# 3V3.net
KiCad netlist of a schematic drawn in Altium Designer
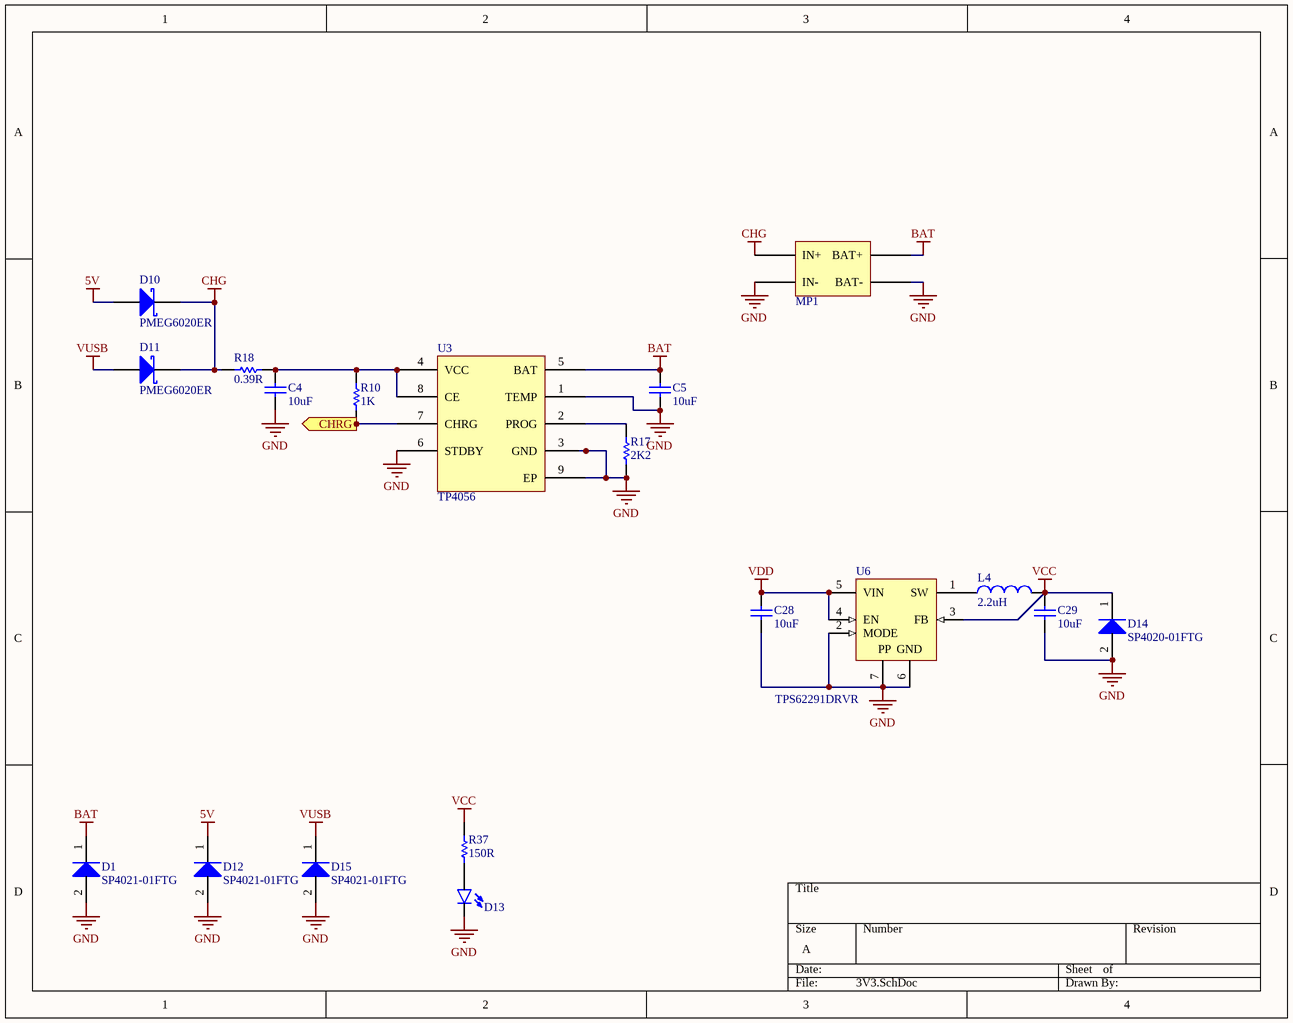
[diagram p0: 3V3.SchDoc]

(export (version "E")
  (design (tool "Eeschema 10.0.6"))
  (components
    (comp (ref "C4")
      (value "10uF")
      (footprint "C1206[3216X160]")
      (description "10uF 50V 20% 1206 (3216 Metric)")
      (fields (field (name "PARTNUMBER") "UMK316BBJ106ML-T") (field (name "MANUFACTURER") "Taiyo Yuden"))
      (libsource (lib "Capacitors") (part "CAP_10uF_50V_1206_20%"))
    )
    (comp (ref "C5")
      (value "10uF")
      (footprint "C1206[3216X160]")
      (description "10uF 50V 20% 1206 (3216 Metric)")
      (fields (field (name "PARTNUMBER") "UMK316BBJ106ML-T") (field (name "MANUFACTURER") "Taiyo Yuden"))
      (libsource (lib "Capacitors") (part "CAP_10uF_50V_1206_20%"))
    )
    (comp (ref "C28")
      (value "10uF")
      (footprint "C0603[1608X92]")
      (description "10uF 16V 10% 0603 (1608 Metric)")
      (fields (field (name "PARTNUMBER") "GRM188R61C106KAALD") (field (name "MANUFACTURER") "Murata"))
      (libsource (lib "Capacitors") (part "CAP_10uF_16V_0603_10%"))
    )
    (comp (ref "C29")
      (value "10uF")
      (footprint "C0603[1608X92]")
      (description "10uF 6.3V 10% 0603 (1608 Metric)")
      (fields (field (name "PARTNUMBER") "GRM188R60J106KE47D") (field (name "MANUFACTURER") "Murata"))
      (libsource (lib "Capacitors") (part "CAP_10uF_6.3V_0603_10%"))
    )
    (comp (ref "D1")
      (value "SP4021-01FTG")
      (footprint "SOD-323")
      (fields (field (name "MANUFACTURER") "Littelfuse"))
      (libsource (lib "Diodes") (part "SP4021-01FTG"))
    )
    (comp (ref "D10")
      (value "PMEG6020ER")
      (footprint "SOD-123")
      (fields (field (name "PARTNUMBER") "PMEG6020ER,115") (field (name "MANUFACTURER") "NXP Semiconductors"))
      (libsource (lib "Diodes") (part "PMEG6020ER"))
    )
    (comp (ref "D11")
      (value "PMEG6020ER")
      (footprint "SOD-123")
      (fields (field (name "PARTNUMBER") "PMEG6020ER,115") (field (name "MANUFACTURER") "NXP Semiconductors"))
      (libsource (lib "Diodes") (part "PMEG6020ER"))
    )
    (comp (ref "D12")
      (value "SP4021-01FTG")
      (footprint "SOD-323")
      (fields (field (name "MANUFACTURER") "Littelfuse"))
      (libsource (lib "Diodes") (part "SP4021-01FTG"))
    )
    (comp (ref "D13")
      (value "LED_0603_GREEN_5mA")
      (footprint "LED0603")
      (fields (field (name "PARTNUMBER") "LTST-C193TGKT-5A") (field (name "MANUFACTURER") "Lite-On Inc."))
      (libsource (lib "LEDs") (part "LED_0603_GREEN_5mA"))
    )
    (comp (ref "D14")
      (value "SP4020-01FTG")
      (footprint "SOD-323")
      (fields (field (name "MANUFACTURER") "Littelfuse"))
      (libsource (lib "Diodes") (part "SP4020-01FTG"))
    )
    (comp (ref "D15")
      (value "SP4021-01FTG")
      (footprint "SOD-323")
      (fields (field (name "MANUFACTURER") "Littelfuse"))
      (libsource (lib "Diodes") (part "SP4021-01FTG"))
    )
    (comp (ref "L4")
      (value "2.2uH")
      (footprint "IND0805")
      (description "2.2uH 20% 1.7A 0805")
      (fields (field (name "PARTNUMBER") "LQM21PN2R2MGHL") (field (name "MANUFACTURER") "Murata"))
      (libsource (lib "Inductors") (part "IND_2.2uH_1.7A_0805_20%"))
    )
    (comp (ref "MP1")
      (value "Li-ion CHARGER")
      (footprint "LI-ION CHARGER")
      (description "TP4056 LI-ION, LI-POLYMER 1-CELL CHARGER")
      (fields (field (name "MANUFACTURER") "ELEPARTS") (field (name "PARTNUMBER") "Micro USB 1A"))
      (libsource (lib "Components") (part "Li-ion CHARGER"))
    )
    (comp (ref "R10")
      (value "1K")
      (footprint "R0603[1608]")
      (description "1K 0.25W 1% 0603 (1005 Metric)")
      (fields (field (name "MANUFACTURER") "Vishay / Dale") (field (name "PARTNUMBER") "CRCW06031K00FKEAHP"))
      (libsource (lib "Resistors") (part "RES_1K_0603_1%"))
    )
    (comp (ref "R17")
      (value "2K2")
      (footprint "R0603[1608]")
      (description "2K2 0.25W 1% 0603 (1005 Metric)")
      (fields (field (name "MANUFACTURER") "Vishay / Dale") (field (name "PARTNUMBER") "CRCW06032K20FKEAHP"))
      (libsource (lib "Resistors") (part "RES_2K2_0603_1%"))
    )
    (comp (ref "R18")
      (value "0.39R")
      (footprint "R1206[3216]")
      (description "0.39R 0.5W 1% 1206 (3216 Metric)")
      (fields (field (name "MANUFACTURER") "Vishay Dale") (field (name "PARTNUMBER") "RCWE1206R390FKEA"))
      (libsource (lib "Resistors") (part "RES_0.39R_1206_1%"))
    )
    (comp (ref "R37")
      (value "150R")
      (footprint "R0603[1608]")
      (description "150R 0.25W 1% 0603 (1005 Metric)")
      (fields (field (name "MANUFACTURER") "Vishay / Dale") (field (name "PARTNUMBER") "CRCW0603150RFKEAHP"))
      (libsource (lib "Resistors") (part "RES_150R_0603_1%"))
    )
    (comp (ref "U3")
      (value "TP4056")
      (footprint "SOIC-8-EP")
      (description "1 CELL Li-ion Battery Charger")
      (fields (field (name "MANUFACTURER") "Nanjing Extension Microelectronics"))
      (libsource (lib "ICs") (part "TP4056"))
    )
    (comp (ref "U6")
      (value "TPS62291DRVR")
      (footprint "WSON-6")
      (description "Voltage Regulators - Switching Regulators 2.25MHz 1A Step-Down Cnvrtr 3.3V Output")
      (fields (field (name "MANUFACTURER") "Texas Instruments"))
      (libsource (lib "ICs") (part "TPS62291DRVR"))
    )
  )
  (nets
    (net (code "1") (name "/CHRG") (class "Default")
      (node (ref "R10") (pin "1") (pinfunction "1_1") (pintype "passive"))
      (node (ref "U3") (pin "7") (pinfunction "CHRG_7") (pintype "passive"))
    )
    (net (code "2") (name "5V") (class "Default")
      (node (ref "D10") (pin "2") (pinfunction "A_2") (pintype "passive"))
      (node (ref "D12") (pin "1") (pinfunction "K_1") (pintype "passive"))
    )
    (net (code "3") (name "BAT") (class "Default")
      (node (ref "C5") (pin "2") (pinfunction "2_2") (pintype "passive"))
      (node (ref "D1") (pin "1") (pinfunction "K_1") (pintype "passive"))
      (node (ref "MP1") (pin "3") (pinfunction "BAT+_3") (pintype "passive"))
      (node (ref "U3") (pin "5") (pinfunction "BAT_5") (pintype "passive"))
    )
    (net (code "4") (name "CHG") (class "Default")
      (node (ref "D10") (pin "1") (pinfunction "K_1") (pintype "passive"))
      (node (ref "D11") (pin "1") (pinfunction "K_1") (pintype "passive"))
      (node (ref "MP1") (pin "1") (pinfunction "IN+_1") (pintype "passive"))
      (node (ref "R18") (pin "2") (pinfunction "2_2") (pintype "passive"))
    )
    (net (code "5") (name "GND") (class "Default")
      (node (ref "C28") (pin "1") (pinfunction "1_1") (pintype "passive"))
      (node (ref "C29") (pin "1") (pinfunction "1_1") (pintype "passive"))
      (node (ref "C4") (pin "1") (pinfunction "1_1") (pintype "passive"))
      (node (ref "C5") (pin "1") (pinfunction "1_1") (pintype "passive"))
      (node (ref "D1") (pin "2") (pinfunction "A_2") (pintype "passive"))
      (node (ref "D12") (pin "2") (pinfunction "A_2") (pintype "passive"))
      (node (ref "D13") (pin "C") (pinfunction "C_C") (pintype "passive"))
      (node (ref "D14") (pin "2") (pinfunction "A_2") (pintype "passive"))
      (node (ref "D15") (pin "2") (pinfunction "A_2") (pintype "passive"))
      (node (ref "MP1") (pin "2") (pinfunction "IN-_2") (pintype "passive"))
      (node (ref "MP1") (pin "4") (pinfunction "BAT-_4") (pintype "passive"))
      (node (ref "R17") (pin "1") (pinfunction "1_1") (pintype "passive"))
      (node (ref "U3") (pin "1") (pinfunction "TEMP_1") (pintype "passive"))
      (node (ref "U3") (pin "3") (pinfunction "GND_3") (pintype "passive"))
      (node (ref "U3") (pin "6") (pinfunction "STDBY_6") (pintype "passive"))
      (node (ref "U3") (pin "9") (pinfunction "EP_9") (pintype "passive"))
      (node (ref "U6") (pin "2") (pinfunction "MODE_2") (pintype "input"))
      (node (ref "U6") (pin "6") (pinfunction "GND_6") (pintype "power_in"))
      (node (ref "U6") (pin "7") (pinfunction "EP_7") (pintype "passive"))
    )
    (net (code "6") (name "Net-(D13-PadA)") (class "Default")
      (node (ref "D13") (pin "A") (pinfunction "A_A") (pintype "passive"))
      (node (ref "R37") (pin "1") (pinfunction "1_1") (pintype "passive"))
    )
    (net (code "7") (name "Net-(U3-CE)") (class "Default")
      (node (ref "C4") (pin "2") (pinfunction "2_2") (pintype "passive"))
      (node (ref "R10") (pin "2") (pinfunction "2_2") (pintype "passive"))
      (node (ref "R18") (pin "1") (pinfunction "1_1") (pintype "passive"))
      (node (ref "U3") (pin "4") (pinfunction "VCC_4") (pintype "passive"))
      (node (ref "U3") (pin "8") (pinfunction "CE_8") (pintype "passive"))
    )
    (net (code "8") (name "Net-(U3-PROG)") (class "Default")
      (node (ref "R17") (pin "2") (pinfunction "2_2") (pintype "passive"))
      (node (ref "U3") (pin "2") (pinfunction "PROG_2") (pintype "passive"))
    )
    (net (code "9") (name "Net-(U6-SW)") (class "Default")
      (node (ref "L4") (pin "1") (pinfunction "1_1") (pintype "passive"))
      (node (ref "U6") (pin "1") (pinfunction "SW_1") (pintype "power_in"))
    )
    (net (code "10") (name "VCC") (class "Default")
      (node (ref "C29") (pin "2") (pinfunction "2_2") (pintype "passive"))
      (node (ref "D14") (pin "1") (pinfunction "K_1") (pintype "passive"))
      (node (ref "L4") (pin "2") (pinfunction "2_2") (pintype "passive"))
      (node (ref "R37") (pin "2") (pinfunction "2_2") (pintype "passive"))
      (node (ref "U6") (pin "3") (pinfunction "FB_3") (pintype "input"))
    )
    (net (code "11") (name "VDD") (class "Default")
      (node (ref "C28") (pin "2") (pinfunction "2_2") (pintype "passive"))
      (node (ref "U6") (pin "4") (pinfunction "EN_4") (pintype "input"))
      (node (ref "U6") (pin "5") (pinfunction "VIN_5") (pintype "power_in"))
    )
    (net (code "12") (name "VUSB") (class "Default")
      (node (ref "D11") (pin "2") (pinfunction "A_2") (pintype "passive"))
      (node (ref "D15") (pin "1") (pinfunction "K_1") (pintype "passive"))
    )
  )
)
